# LED_Board.net
KiCad netlist of a schematic drawn in EAGLE
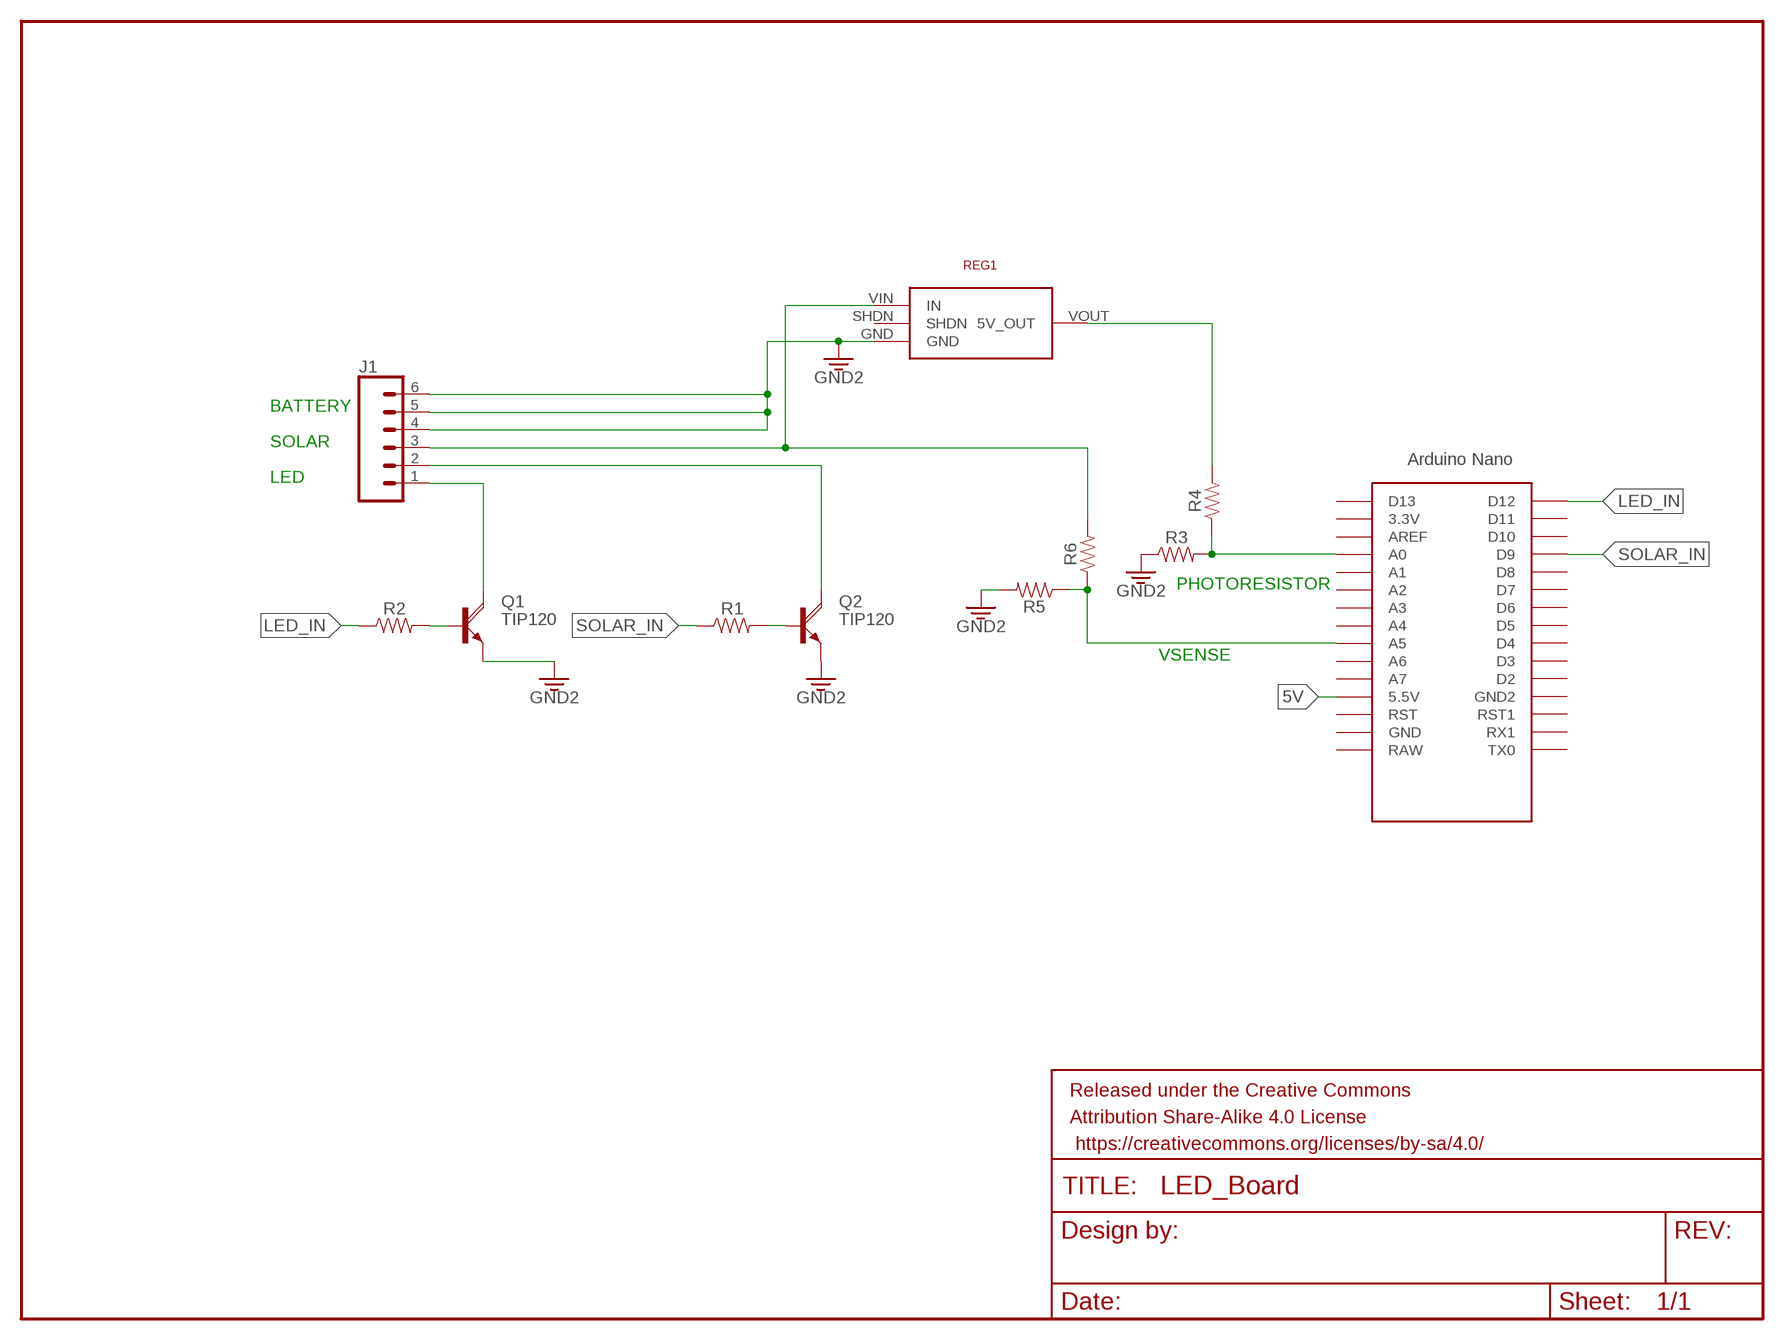
[diagram p0: schematic, sheet 1]

(export (version "E")
  (design (tool "Eeschema 10.0.6"))
  (components
    (comp (ref "FRAME1")
      (value "FRAME-LETTER")
      (footprint "eagle-import:CREATIVE_COMMONS")
      (libsource (lib "eagle-import") (part "FRAME-LETTER"))
    )
    (comp (ref "J1")
      (value "CONN_063.5MM-6")
      (footprint "eagle-import:SCREWTERMINAL-3.5MM-6")
      (libsource (lib "eagle-import") (part "CONN_063.5MM-6"))
    )
    (comp (ref "Q1")
      (value "TIP120")
      (footprint "eagle-import:TO220AH")
      (libsource (lib "eagle-import") (part "TIP120"))
    )
    (comp (ref "Q2")
      (value "TIP120")
      (footprint "eagle-import:TO220AH")
      (libsource (lib "eagle-import") (part "TIP120"))
    )
    (comp (ref "R1")
      (value "RESISTORAXIAL-0.3")
      (footprint "eagle-import:AXIAL-0.3")
      (libsource (lib "eagle-import") (part "RESISTORAXIAL-0.3"))
    )
    (comp (ref "R2")
      (value "RESISTORAXIAL-0.3")
      (footprint "eagle-import:AXIAL-0.3")
      (libsource (lib "eagle-import") (part "RESISTORAXIAL-0.3"))
    )
    (comp (ref "R3")
      (value "RESISTORAXIAL-0.3")
      (footprint "eagle-import:AXIAL-0.3")
      (libsource (lib "eagle-import") (part "RESISTORAXIAL-0.3"))
    )
    (comp (ref "R4")
      (value "RESISTORAXIAL-0.3")
      (footprint "eagle-import:AXIAL-0.3")
      (libsource (lib "eagle-import") (part "RESISTORAXIAL-0.3"))
    )
    (comp (ref "R5")
      (value "RESISTORAXIAL-0.3")
      (footprint "eagle-import:AXIAL-0.3")
      (libsource (lib "eagle-import") (part "RESISTORAXIAL-0.3"))
    )
    (comp (ref "R6")
      (value "RESISTORAXIAL-0.3")
      (footprint "eagle-import:AXIAL-0.3")
      (libsource (lib "eagle-import") (part "RESISTORAXIAL-0.3"))
    )
    (comp (ref "REG1")
      (value "POLOLU_D24V3F5")
      (footprint "eagle-import:POLOLU_D24V3F5")
      (libsource (lib "eagle-import") (part "POLOLU_D24V3F5"))
    )
    (comp (ref "U$1")
      (value "NANO")
      (footprint "eagle-import:NANO")
      (libsource (lib "eagle-import") (part "NANO"))
    )
  )
  (nets
    (net (code "1") (name "5V") (class "Default")
      (node (ref "R4") (pin "P$2") (pinfunction "2_P$2") (pintype "passive"))
      (node (ref "REG1") (pin "VOUT") (pinfunction "5V_OUT_VOUT") (pintype "bidirectional"))
      (node (ref "U$1") (pin "5V") (pinfunction "5.5V_5V") (pintype "bidirectional"))
    )
    (net (code "2") (name "GND2") (class "Default")
      (node (ref "J1") (pin "4") (pinfunction "4_4") (pintype "passive"))
      (node (ref "J1") (pin "5") (pinfunction "5_5") (pintype "passive"))
      (node (ref "J1") (pin "6") (pinfunction "6_6") (pintype "passive"))
      (node (ref "Q1") (pin "E") (pinfunction "E_E") (pintype "passive"))
      (node (ref "Q2") (pin "E") (pinfunction "E_E") (pintype "passive"))
      (node (ref "R3") (pin "P$1") (pinfunction "1_P$1") (pintype "passive"))
      (node (ref "R5") (pin "P$2") (pinfunction "2_P$2") (pintype "passive"))
      (node (ref "REG1") (pin "GND") (pinfunction "GND_GND") (pintype "bidirectional"))
    )
    (net (code "3") (name "LED_IN") (class "Default")
      (node (ref "R2") (pin "P$1") (pinfunction "1_P$1") (pintype "passive"))
      (node (ref "U$1") (pin "D12") (pinfunction "D12_D12") (pintype "bidirectional"))
    )
    (net (code "4") (name "Net-(J1-Pad1)") (class "Default")
      (node (ref "J1") (pin "1") (pinfunction "1_1") (pintype "passive"))
      (node (ref "Q1") (pin "C") (pinfunction "C_C") (pintype "passive"))
    )
    (net (code "5") (name "Net-(J1-Pad2)") (class "Default")
      (node (ref "J1") (pin "2") (pinfunction "2_2") (pintype "passive"))
      (node (ref "Q2") (pin "C") (pinfunction "C_C") (pintype "passive"))
    )
    (net (code "6") (name "Net-(R1-2)") (class "Default")
      (node (ref "Q2") (pin "B") (pinfunction "B_B") (pintype "passive"))
      (node (ref "R1") (pin "P$2") (pinfunction "2_P$2") (pintype "passive"))
    )
    (net (code "7") (name "Net-(R2-2)") (class "Default")
      (node (ref "Q1") (pin "B") (pinfunction "B_B") (pintype "passive"))
      (node (ref "R2") (pin "P$2") (pinfunction "2_P$2") (pintype "passive"))
    )
    (net (code "8") (name "Net-(R3-2)") (class "Default")
      (node (ref "R3") (pin "P$2") (pinfunction "2_P$2") (pintype "passive"))
      (node (ref "R4") (pin "P$1") (pinfunction "1_P$1") (pintype "passive"))
      (node (ref "U$1") (pin "A0") (pinfunction "A0_A0") (pintype "bidirectional"))
    )
    (net (code "9") (name "Net-(R5-1)") (class "Default")
      (node (ref "R5") (pin "P$1") (pinfunction "1_P$1") (pintype "passive"))
      (node (ref "R6") (pin "P$1") (pinfunction "1_P$1") (pintype "passive"))
      (node (ref "U$1") (pin "A5") (pinfunction "A5_A5") (pintype "bidirectional"))
    )
    (net (code "10") (name "Net-(R6-2)") (class "Default")
      (node (ref "J1") (pin "3") (pinfunction "3_3") (pintype "passive"))
      (node (ref "R6") (pin "P$2") (pinfunction "2_P$2") (pintype "passive"))
      (node (ref "REG1") (pin "VIN") (pinfunction "IN_VIN") (pintype "bidirectional"))
    )
    (net (code "11") (name "SOLAR_IN") (class "Default")
      (node (ref "R1") (pin "P$1") (pinfunction "1_P$1") (pintype "passive"))
      (node (ref "U$1") (pin "D9") (pinfunction "D9_D9") (pintype "bidirectional"))
    )
    (net (code "12") (name "unconnected-(REG1-PadSHDN)") (class "Default")
      (node (ref "REG1") (pin "SHDN") (pinfunction "SHDN_SHDN") (pintype "bidirectional"))
    )
    (net (code "13") (name "unconnected-(U$1-GND2-PadGND1)") (class "Default")
      (node (ref "U$1") (pin "GND1") (pinfunction "GND2_GND1") (pintype "bidirectional"))
    )
    (net (code "14") (name "unconnected-(U$1-Pad3.3V)") (class "Default")
      (node (ref "U$1") (pin "3.3V") (pinfunction "3.3V_3.3V") (pintype "bidirectional"))
    )
    (net (code "15") (name "unconnected-(U$1-PadA1)") (class "Default")
      (node (ref "U$1") (pin "A1") (pinfunction "A1_A1") (pintype "bidirectional"))
    )
    (net (code "16") (name "unconnected-(U$1-PadA2)") (class "Default")
      (node (ref "U$1") (pin "A2") (pinfunction "A2_A2") (pintype "bidirectional"))
    )
    (net (code "17") (name "unconnected-(U$1-PadA3)") (class "Default")
      (node (ref "U$1") (pin "A3") (pinfunction "A3_A3") (pintype "bidirectional"))
    )
    (net (code "18") (name "unconnected-(U$1-PadA4)") (class "Default")
      (node (ref "U$1") (pin "A4") (pinfunction "A4_A4") (pintype "bidirectional"))
    )
    (net (code "19") (name "unconnected-(U$1-PadA6)") (class "Default")
      (node (ref "U$1") (pin "A6") (pinfunction "A6_A6") (pintype "bidirectional"))
    )
    (net (code "20") (name "unconnected-(U$1-PadA7)") (class "Default")
      (node (ref "U$1") (pin "A7") (pinfunction "A7_A7") (pintype "bidirectional"))
    )
    (net (code "21") (name "unconnected-(U$1-PadAREF)") (class "Default")
      (node (ref "U$1") (pin "AREF") (pinfunction "AREF_AREF") (pintype "bidirectional"))
    )
    (net (code "22") (name "unconnected-(U$1-PadD2)") (class "Default")
      (node (ref "U$1") (pin "D2") (pinfunction "D2_D2") (pintype "bidirectional"))
    )
    (net (code "23") (name "unconnected-(U$1-PadD3)") (class "Default")
      (node (ref "U$1") (pin "D3") (pinfunction "D3_D3") (pintype "bidirectional"))
    )
    (net (code "24") (name "unconnected-(U$1-PadD4)") (class "Default")
      (node (ref "U$1") (pin "D4") (pinfunction "D4_D4") (pintype "bidirectional"))
    )
    (net (code "25") (name "unconnected-(U$1-PadD5)") (class "Default")
      (node (ref "U$1") (pin "D5") (pinfunction "D5_D5") (pintype "bidirectional"))
    )
    (net (code "26") (name "unconnected-(U$1-PadD6)") (class "Default")
      (node (ref "U$1") (pin "D6") (pinfunction "D6_D6") (pintype "bidirectional"))
    )
    (net (code "27") (name "unconnected-(U$1-PadD7)") (class "Default")
      (node (ref "U$1") (pin "D7") (pinfunction "D7_D7") (pintype "bidirectional"))
    )
    (net (code "28") (name "unconnected-(U$1-PadD8)") (class "Default")
      (node (ref "U$1") (pin "D8") (pinfunction "D8_D8") (pintype "bidirectional"))
    )
    (net (code "29") (name "unconnected-(U$1-PadD10)") (class "Default")
      (node (ref "U$1") (pin "D10") (pinfunction "D10_D10") (pintype "bidirectional"))
    )
    (net (code "30") (name "unconnected-(U$1-PadD11)") (class "Default")
      (node (ref "U$1") (pin "D11") (pinfunction "D11_D11") (pintype "bidirectional"))
    )
    (net (code "31") (name "unconnected-(U$1-PadD13)") (class "Default")
      (node (ref "U$1") (pin "D13") (pinfunction "D13_D13") (pintype "bidirectional"))
    )
    (net (code "32") (name "unconnected-(U$1-PadGND)") (class "Default")
      (node (ref "U$1") (pin "GND") (pinfunction "GND_GND") (pintype "bidirectional"))
    )
    (net (code "33") (name "unconnected-(U$1-PadICSP1)") (class "Default")
      (node (ref "U$1") (pin "ICSP1") (pinfunction "ICSP1_ICSP1") (pintype "bidirectional"))
    )
    (net (code "34") (name "unconnected-(U$1-PadICSP2)") (class "Default")
      (node (ref "U$1") (pin "ICSP2") (pinfunction "ICSP2_ICSP2") (pintype "bidirectional"))
    )
    (net (code "35") (name "unconnected-(U$1-PadICSP3)") (class "Default")
      (node (ref "U$1") (pin "ICSP3") (pinfunction "ICSP3_ICSP3") (pintype "bidirectional"))
    )
    (net (code "36") (name "unconnected-(U$1-PadICSP4)") (class "Default")
      (node (ref "U$1") (pin "ICSP4") (pinfunction "ICSP4_ICSP4") (pintype "bidirectional"))
    )
    (net (code "37") (name "unconnected-(U$1-PadICSP5)") (class "Default")
      (node (ref "U$1") (pin "ICSP5") (pinfunction "ICSP5_ICSP5") (pintype "bidirectional"))
    )
    (net (code "38") (name "unconnected-(U$1-PadICSP6)") (class "Default")
      (node (ref "U$1") (pin "ICSP6") (pinfunction "ICSP6_ICSP6") (pintype "bidirectional"))
    )
    (net (code "39") (name "unconnected-(U$1-PadRAW)") (class "Default")
      (node (ref "U$1") (pin "RAW") (pinfunction "RAW_RAW") (pintype "bidirectional"))
    )
    (net (code "40") (name "unconnected-(U$1-PadRST)") (class "Default")
      (node (ref "U$1") (pin "RST") (pinfunction "RST_RST") (pintype "bidirectional"))
    )
    (net (code "41") (name "unconnected-(U$1-PadRST1)") (class "Default")
      (node (ref "U$1") (pin "RST1") (pinfunction "RST1_RST1") (pintype "bidirectional"))
    )
    (net (code "42") (name "unconnected-(U$1-PadRX1)") (class "Default")
      (node (ref "U$1") (pin "RX1") (pinfunction "RX1_RX1") (pintype "bidirectional"))
    )
    (net (code "43") (name "unconnected-(U$1-PadTX0)") (class "Default")
      (node (ref "U$1") (pin "TX0") (pinfunction "TX0_TX0") (pintype "bidirectional"))
    )
  )
)
